# SAMC21_Xplained_Pro_dual_input_power_sup.net
KiCad netlist of a schematic drawn in Altium Designer
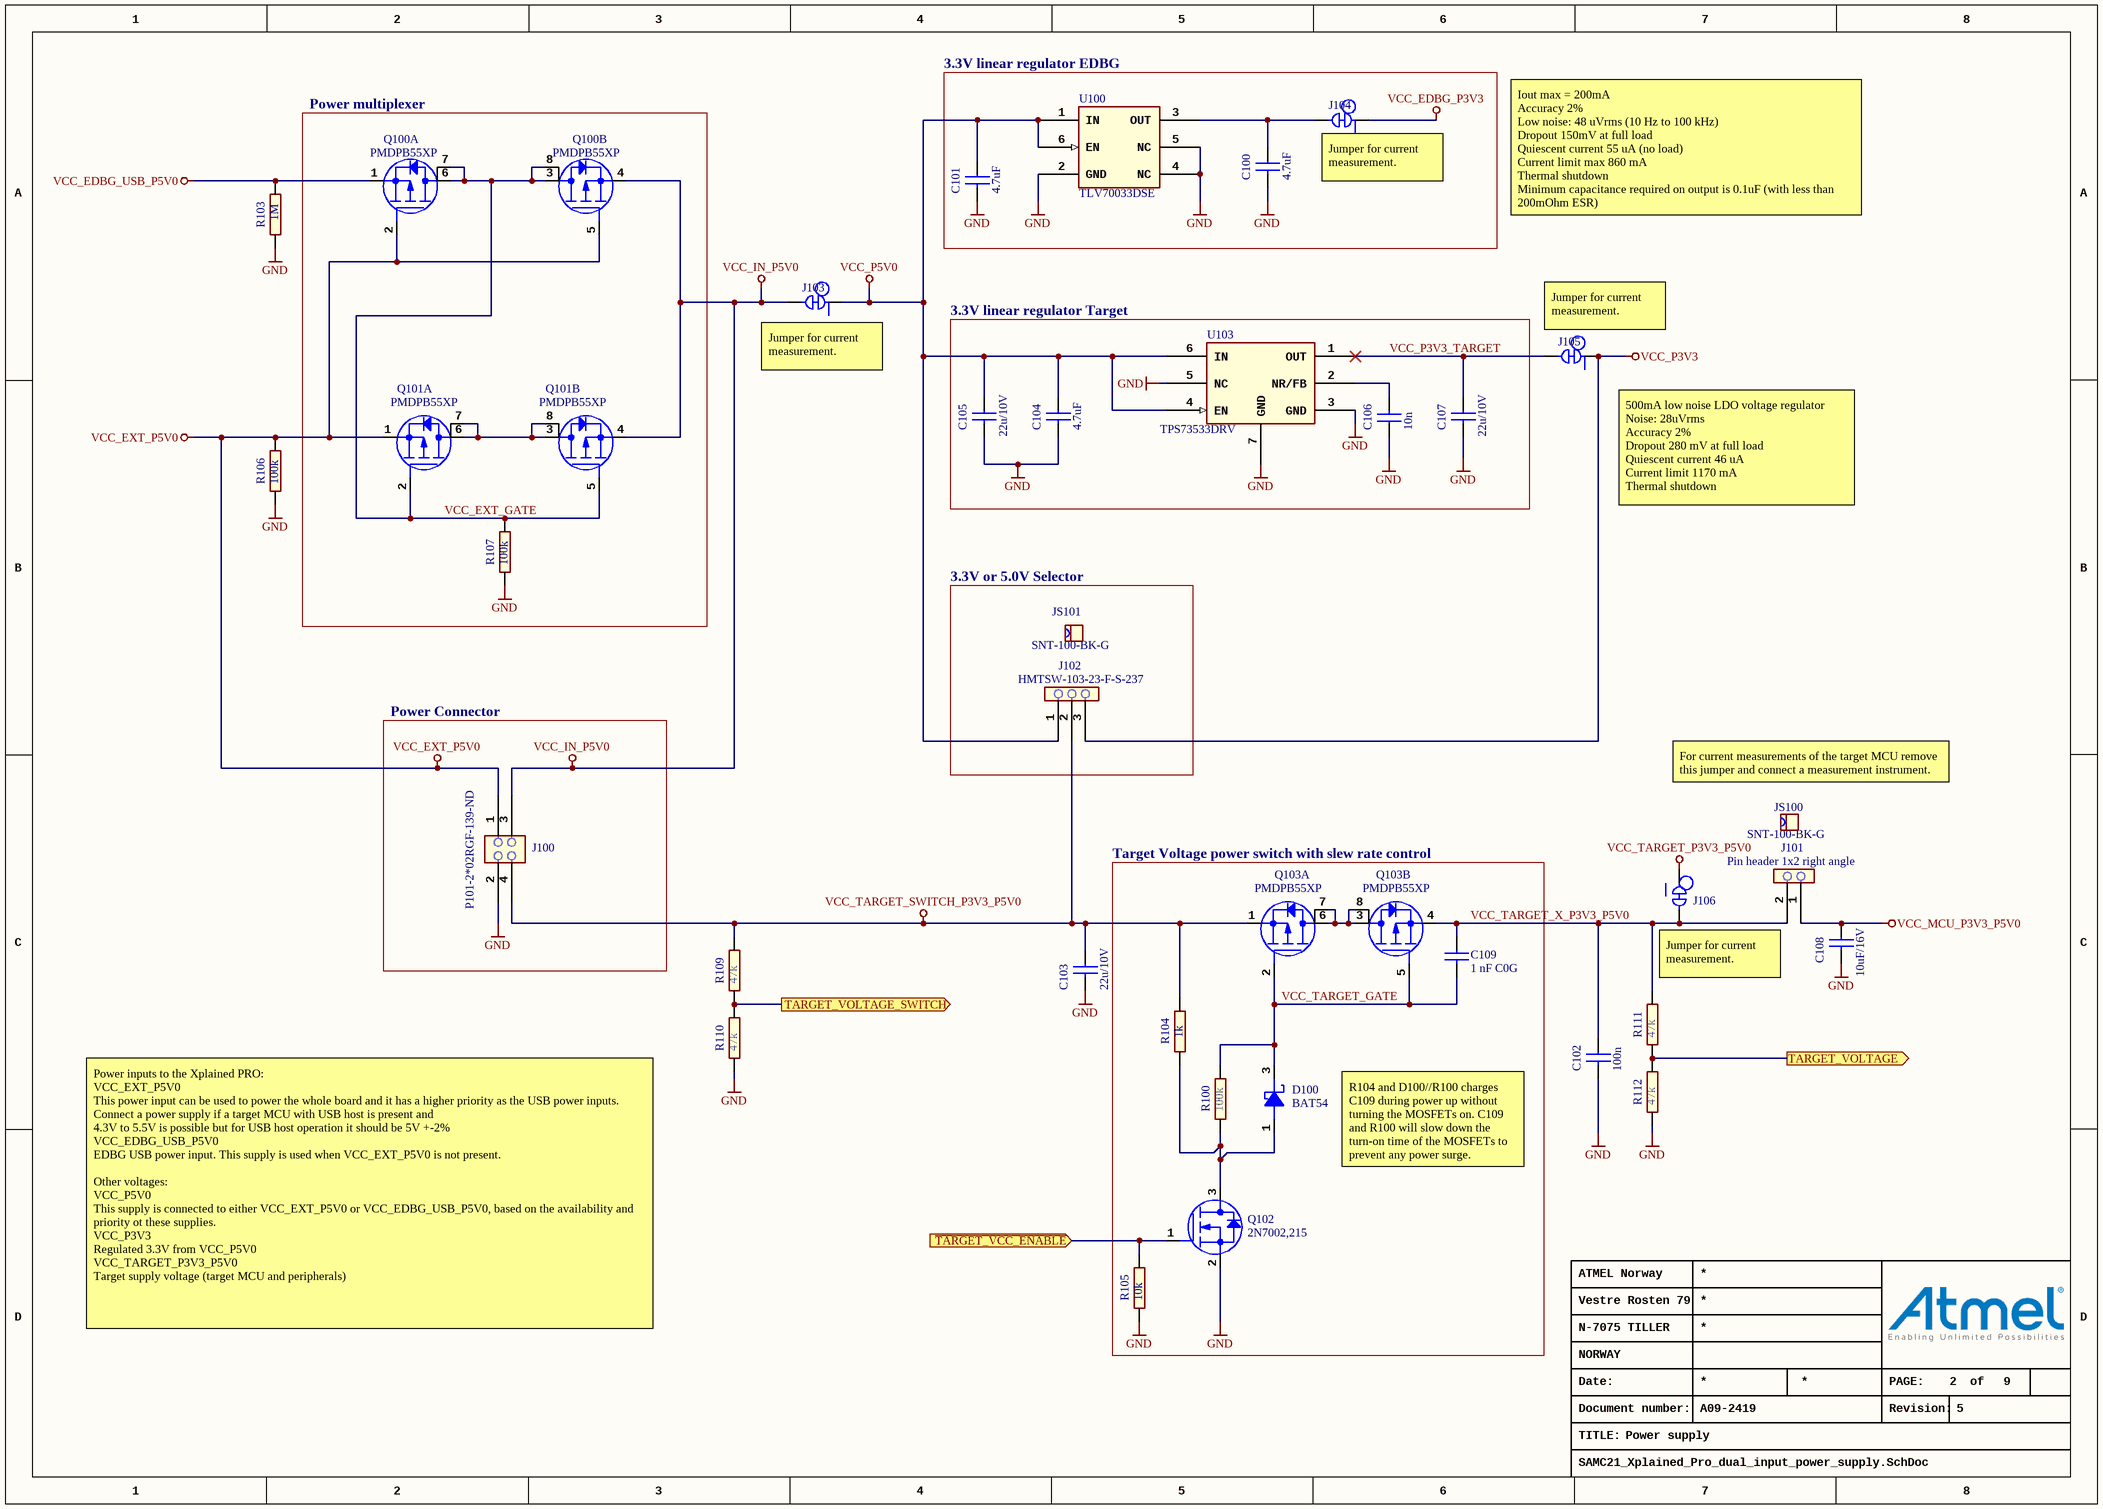
[diagram p0: SAMC21_Xplained_Pro_dual_input_power_supply.SchDoc]

(export (version "E")
  (design (tool "Eeschema 10.0.6"))
  (components
    (comp (ref "C100")
      (value "4.7uF")
      (footprint "AP1-00117")
      (description "Ceramic capacitor, SMD 0603, X5R, 10V, 10% (de31036)")
      (fields (field (name "TOLERANCE") "10%") (field (name "MANUFACTURER") "tdk"))
      (libsource (lib "AltiumDbLib") (part "CAP-NONPOL"))
    )
    (comp (ref "C101")
      (value "4.7uF")
      (footprint "AP1-00117")
      (description "Ceramic capacitor, SMD 0603, X5R, 10V, 10% (de31036)")
      (fields (field (name "TOLERANCE") "10%") (field (name "MANUFACTURER") "tdk"))
      (libsource (lib "AltiumDbLib") (part "CAP-NONPOL"))
    )
    (comp (ref "C102")
      (value "100n")
      (footprint "AP1-00001")
      (description "Ceramic capacitor, SMD 0402, X7R, 16V, +/-10%")
      (fields (field (name "TOLERANCE") "16V, +/-10%") (field (name "MANUFACTURER") "Kemet"))
      (libsource (lib "AltiumDbLib") (part "CAP-NONPOL"))
    )
    (comp (ref "C103")
      (value "22u/10V")
      (footprint "AP1-00003")
      (description "Ceramic capacitor, SMD 0805, X5R, 10V, Â±20%")
      (fields (field (name "MANUFACTURER") "tdk") (field (name "MPN") "C2012X5R1A226M/0.85"))
      (libsource (lib "AltiumDbLib") (part "CAP-NONPOL"))
    )
    (comp (ref "C104")
      (value "4.7uF")
      (footprint "AP1-00117")
      (description "Ceramic capacitor, SMD 0603, X5R, 10V, 10% (de31036)")
      (fields (field (name "TOLERANCE") "10%") (field (name "MANUFACTURER") "tdk"))
      (libsource (lib "AltiumDbLib") (part "CAP-NONPOL"))
    )
    (comp (ref "C105")
      (value "22u/10V")
      (footprint "AP1-00003")
      (description "Ceramic capacitor, SMD 0805, X5R, 10V, Â±20%")
      (fields (field (name "MANUFACTURER") "tdk") (field (name "MPN") "C2012X5R1A226M/0.85"))
      (libsource (lib "AltiumDbLib") (part "CAP-NONPOL"))
    )
    (comp (ref "C106")
      (value "10n")
      (footprint "AP1-00053")
      (description "Ceramic capacitor, SMD 0402, X7R, 25V, +/-10%")
      (fields (field (name "TOLERANCE") "25V, +/-10%"))
      (libsource (lib "AltiumDbLib") (part "CAP-NONPOL"))
    )
    (comp (ref "C107")
      (value "22u/10V")
      (footprint "AP1-00003")
      (description "Ceramic capacitor, SMD 0805, X5R, 10V, Â±20%")
      (fields (field (name "MANUFACTURER") "tdk") (field (name "MPN") "C2012X5R1A226M/0.85"))
      (libsource (lib "AltiumDbLib") (part "CAP-NONPOL"))
    )
    (comp (ref "C108")
      (value "10uF/16V")
      (footprint "AP1-00039")
      (description "Ceramic capacitor, SMD 0603, X5R, 16V, 10UF ± 20% (High Density)")
      (fields (field (name "TOLERANCE") "­± 20%") (field (name "MANUFACTURER") "Taiyo Yuden"))
      (libsource (lib "AltiumDbLib") (part "CAP-NONPOL"))
    )
    (comp (ref "C109")
      (value "1 nF C0G")
      (footprint "AP1-00053")
      (description "Ceramic capacitor, SMD 0402, C0G, 50V, +/-5%")
      (fields (field (name "TOLERANCE") "5%") (field (name "MANUFACTURER") "Murata"))
      (libsource (lib "AltiumDbLib") (part "CAP-NONPOL"))
    )
    (comp (ref "D100")
      (value "BAT54")
      (footprint "AP4-00007")
      (fields (field (name "MANUFACTURER") "Philips"))
      (libsource (lib "AltiumDbLib") (part "SCHOTTKY_SMD_31"))
    )
    (comp (ref "J100")
      (value "P101-2*02RGF-139-ND")
      (footprint "AP8-00628")
      (description "Pin header, 2x2, Right Angle, 2.54mm, THT, Pin In Paste")
      (fields (field (name "MANUFACTURER") "Pro-data International Corp"))
      (libsource (lib "AltiumDbLib") (part "HEADER 2x2"))
    )
    (comp (ref "J101")
      (value "Pin header 1x2 right angle")
      (footprint "AP8-00367")
      (description "1x2 pin header, right angle, 2.54 mm pitch, through-hole")
      (fields (field (name "MANUFACTURER") "Pro-data International Corp") (field (name "MPN") "2213R-2G"))
      (libsource (lib "AltiumDbLib") (part "HEADER 1x2"))
    )
    (comp (ref "J102")
      (value "HMTSW-103-23-F-S-237")
      (footprint "AP8-00745")
      (description "1x3 pin header, 2.54mm pitch, Pin-in-Paste THM, 1mm hole")
      (fields (field (name "MANUFACTURER") "SAMTEC"))
      (libsource (lib "AltiumDbLib") (part "HEADER 1x3"))
    )
    (comp (ref "J103")
      (value "~")
      (footprint "AP9-00044")
      (description "Default closed SMD strap, 0603 size")
      (libsource (lib "AltiumDbLib") (part "SMD-STRAP_CLOSED"))
    )
    (comp (ref "J104")
      (value "~")
      (footprint "AP9-00044")
      (description "Default closed SMD strap, 0603 size")
      (libsource (lib "AltiumDbLib") (part "SMD-STRAP_CLOSED"))
    )
    (comp (ref "J105")
      (value "~")
      (footprint "AP9-00044")
      (description "Default closed SMD strap, 0603 size")
      (libsource (lib "AltiumDbLib") (part "SMD-STRAP_CLOSED"))
    )
    (comp (ref "J106")
      (value "~")
      (footprint "AP9-00044")
      (description "Default closed SMD strap, 0603 size")
      (libsource (lib "AltiumDbLib") (part "SMD-STRAP_CLOSED"))
    )
    (comp (ref "JS100")
      (value "SNT-100-BK-G")
      (footprint "AP8-00525")
      (description "Jumper cap for 2.54mm pinheader")
      (fields (field (name "MANUFACTURER") "SAMTEC"))
      (libsource (lib "AltiumDbLib") (part "JUMPER_CAP"))
    )
    (comp (ref "JS101")
      (value "SNT-100-BK-G")
      (footprint "AP8-00525")
      (description "Jumper cap for 2.54mm pinheader")
      (fields (field (name "MANUFACTURER") "SAMTEC"))
      (libsource (lib "AltiumDbLib") (part "JUMPER_CAP"))
    )
    (comp (ref "Q100")
      (value "PMDPB55XP")
      (footprint "AP5-00047")
      (description "Dual P-Channel MOSFET, -20V, RDS(ON) < 55 mOhm @-3.4A@-4.5V")
      (fields (field (name "MANUFACTURER") "NXP") (field (name "Comment") "Farnell order code: 2191806"))
      (libsource (lib "AltiumDbLib") (part "MOSFET_DUAL_P_S1G1D2S2G2D1D1D2"))
    )
    (comp (ref "Q101")
      (value "PMDPB55XP")
      (footprint "AP5-00047")
      (description "Dual P-Channel MOSFET, -20V, RDS(ON) < 55 mOhm @-3.4A@-4.5V")
      (fields (field (name "MANUFACTURER") "NXP") (field (name "Comment") "Farnell order code: 2191806"))
      (libsource (lib "AltiumDbLib") (part "MOSFET_DUAL_P_S1G1D2S2G2D1D1D2"))
    )
    (comp (ref "Q102")
      (value "2N7002,215")
      (footprint "AP5-00002")
      (description "N-Channel MOSFET. 60V, 0.300A continuous, 1.2A Peak. RDS(ON) = 3.8Ohm@VGS=4.5V, VGS(th)<2.5V")
      (fields (field (name "MANUFACTURER") "NXP"))
      (libsource (lib "AltiumDbLib") (part "MOSFET_N_GSD"))
    )
    (comp (ref "Q103")
      (value "PMDPB55XP")
      (footprint "AP5-00047")
      (description "Dual P-Channel MOSFET, -20V, RDS(ON) < 55 mOhm @-3.4A@-4.5V")
      (fields (field (name "MANUFACTURER") "NXP") (field (name "Comment") "Farnell order code: 2191806"))
      (libsource (lib "AltiumDbLib") (part "MOSFET_DUAL_P_S1G1D2S2G2D1D1D2"))
    )
    (comp (ref "R100")
      (value "100k")
      (footprint "AP2-00000")
      (description "Thick film resistor, SMD 0402, 1/16W, 1%")
      (fields (field (name "TOLERANCE") "1 %"))
      (libsource (lib "") (part "R2_1"))
    )
    (comp (ref "R103")
      (value "1M")
      (footprint "AP2-00000")
      (description "Thick film resistor, SMD 0402, 1/16W, 1%")
      (fields (field (name "TOLERANCE") "1 %"))
      (libsource (lib "") (part "R2_1"))
    )
    (comp (ref "R104")
      (value "1k")
      (footprint "AP2-00000")
      (description "Thick film resistor, SMD 0402, 1/16W, 1%")
      (fields (field (name "TOLERANCE") "1 %"))
      (libsource (lib "") (part "R2_1"))
    )
    (comp (ref "R105")
      (value "10k")
      (footprint "AP2-00000")
      (description "Thick film resistor, SMD 0402, 1/16W, 1%")
      (fields (field (name "TOLERANCE") "1 %") (field (name "MANUFACTURER") "vishay"))
      (libsource (lib "") (part "R2_1"))
    )
    (comp (ref "R106")
      (value "100k")
      (footprint "AP2-00000")
      (description "Thick film resistor, SMD 0402, 1/16W, 1%")
      (fields (field (name "TOLERANCE") "1 %"))
      (libsource (lib "") (part "R2_1"))
    )
    (comp (ref "R107")
      (value "100k")
      (footprint "AP2-00000")
      (description "Thick film resistor, SMD 0402, 1/16W, 1%")
      (fields (field (name "TOLERANCE") "1 %"))
      (libsource (lib "") (part "R2_1"))
    )
    (comp (ref "R109")
      (value "47k")
      (footprint "AP2-00000")
      (description "Thick film resistor, SMD 0402, 1/16W, 1%")
      (fields (field (name "TOLERANCE") "1 %"))
      (libsource (lib "AltiumDbLib") (part "R2"))
    )
    (comp (ref "R110")
      (value "47k")
      (footprint "AP2-00000")
      (description "Thick film resistor, SMD 0402, 1/16W, 1%")
      (fields (field (name "TOLERANCE") "1 %"))
      (libsource (lib "AltiumDbLib") (part "R2"))
    )
    (comp (ref "R111")
      (value "47k")
      (footprint "AP2-00000")
      (description "Thick film resistor, SMD 0402, 1/16W, 1%")
      (fields (field (name "TOLERANCE") "1 %"))
      (libsource (lib "AltiumDbLib") (part "R2"))
    )
    (comp (ref "R112")
      (value "47k")
      (footprint "AP2-00000")
      (description "Thick film resistor, SMD 0402, 1/16W, 1%")
      (fields (field (name "TOLERANCE") "1 %"))
      (libsource (lib "AltiumDbLib") (part "R2"))
    )
    (comp (ref "U100")
      (value "TLV70033DSE")
      (footprint "AP6-00262")
      (description "LDO, 200 mA, Iq=31 uA, Vdo=250mV, Vout=3.3V, VIN= 2 V to 5.5V, SON-6 package")
      (fields (field (name "MANUFACTURER") "Texas Instruments"))
      (libsource (lib "AltiumDbLib") (part "TLV70033"))
    )
    (comp (ref "U103")
      (value "TPS73533DRV")
      (footprint "AP6-00162")
      (fields (field (name "MANUFACTURER") "Texas Instruments"))
      (libsource (lib "AltiumDbLib") (part "TPS735xxDRV"))
    )
  )
  (nets
    (net (code "1") (name "/TARGET_VOLTAGE") (class "Default")
      (node (ref "R111") (pin "1") (pinfunction "1_1") (pintype "passive"))
      (node (ref "R112") (pin "2") (pinfunction "2_2") (pintype "passive"))
    )
    (net (code "2") (name "/TARGET_VOLTAGE_SWITCH") (class "Default")
      (node (ref "R109") (pin "1") (pinfunction "1_1") (pintype "passive"))
      (node (ref "R110") (pin "2") (pinfunction "2_2") (pintype "passive"))
    )
    (net (code "3") (name "/VCC_EXT_GATE") (class "Default")
      (node (ref "Q100") (pin "3") (pinfunction "D2_3") (pintype "passive"))
      (node (ref "Q100") (pin "6") (pinfunction "D1_6") (pintype "passive"))
      (node (ref "Q100") (pin "7") (pinfunction "D1_PAD_7") (pintype "passive"))
      (node (ref "Q100") (pin "8") (pinfunction "D2_PAD_8") (pintype "passive"))
      (node (ref "Q101") (pin "2") (pinfunction "G1_2") (pintype "passive"))
      (node (ref "Q101") (pin "5") (pinfunction "G2_5") (pintype "passive"))
      (node (ref "R107") (pin "2") (pinfunction "2_2") (pintype "passive"))
    )
    (net (code "4") (name "/VCC_P3V3_TARGET") (class "Default")
      (node (ref "C107") (pin "1") (pinfunction "1_1") (pintype "passive"))
      (node (ref "J105") (pin "2") (pinfunction "2_2") (pintype "passive"))
      (node (ref "U103") (pin "1") (pinfunction "OUT_1") (pintype "power_in"))
    )
    (net (code "5") (name "/VCC_TARGET_GATE") (class "Default")
      (node (ref "C109") (pin "2") (pinfunction "2_2") (pintype "passive"))
      (node (ref "D100") (pin "3") (pinfunction "CATHODE_3") (pintype "passive"))
      (node (ref "Q103") (pin "2") (pinfunction "G1_2") (pintype "passive"))
      (node (ref "Q103") (pin "5") (pinfunction "G2_5") (pintype "passive"))
      (node (ref "R100") (pin "2") (pinfunction "2_2") (pintype "passive"))
    )
    (net (code "6") (name "/VCC_TARGET_X_P3V3_P5V0") (class "Default")
      (node (ref "C102") (pin "1") (pinfunction "1_1") (pintype "passive"))
      (node (ref "C109") (pin "1") (pinfunction "1_1") (pintype "passive"))
      (node (ref "J101") (pin "2") (pinfunction "2_2") (pintype "passive"))
      (node (ref "J106") (pin "2") (pinfunction "2_2") (pintype "passive"))
      (node (ref "Q103") (pin "4") (pinfunction "S2_4") (pintype "passive"))
      (node (ref "R111") (pin "2") (pinfunction "2_2") (pintype "passive"))
    )
    (net (code "7") (name "/~{TARGET_VCC_ENABLE}") (class "Default")
      (node (ref "Q102") (pin "1") (pinfunction "G_1") (pintype "passive"))
      (node (ref "R105") (pin "2") (pinfunction "2_2") (pintype "passive"))
    )
    (net (code "8") (name "GND") (class "Default")
      (node (ref "C100") (pin "2") (pinfunction "2_2") (pintype "passive"))
      (node (ref "C101") (pin "2") (pinfunction "2_2") (pintype "passive"))
      (node (ref "C102") (pin "2") (pinfunction "2_2") (pintype "passive"))
      (node (ref "C103") (pin "2") (pinfunction "2_2") (pintype "passive"))
      (node (ref "C104") (pin "2") (pinfunction "2_2") (pintype "passive"))
      (node (ref "C105") (pin "2") (pinfunction "2_2") (pintype "passive"))
      (node (ref "C106") (pin "1") (pinfunction "1_1") (pintype "passive"))
      (node (ref "C107") (pin "2") (pinfunction "2_2") (pintype "passive"))
      (node (ref "C108") (pin "2") (pinfunction "2_2") (pintype "passive"))
      (node (ref "J100") (pin "2") (pinfunction "2_2") (pintype "passive"))
      (node (ref "Q102") (pin "2") (pinfunction "S_2") (pintype "passive"))
      (node (ref "R103") (pin "1") (pinfunction "1_1") (pintype "passive"))
      (node (ref "R105") (pin "1") (pinfunction "1_1") (pintype "passive"))
      (node (ref "R106") (pin "1") (pinfunction "1_1") (pintype "passive"))
      (node (ref "R107") (pin "1") (pinfunction "1_1") (pintype "passive"))
      (node (ref "R110") (pin "1") (pinfunction "1_1") (pintype "passive"))
      (node (ref "R112") (pin "1") (pinfunction "1_1") (pintype "passive"))
      (node (ref "U100") (pin "2") (pinfunction "GND_2") (pintype "power_in"))
      (node (ref "U100") (pin "4") (pinfunction "NC_4") (pintype "passive"))
      (node (ref "U100") (pin "5") (pinfunction "NC_5") (pintype "passive"))
      (node (ref "U103") (pin "3") (pinfunction "GND_3") (pintype "power_in"))
      (node (ref "U103") (pin "5") (pinfunction "NC_5") (pintype "passive"))
      (node (ref "U103") (pin "7") (pinfunction "GND_7") (pintype "power_in"))
    )
    (net (code "9") (name "Net-(D100-ANODE)") (class "Default")
      (node (ref "D100") (pin "1") (pinfunction "ANODE_1") (pintype "passive"))
      (node (ref "Q102") (pin "3") (pinfunction "D_3") (pintype "passive"))
      (node (ref "R100") (pin "1") (pinfunction "1_1") (pintype "passive"))
      (node (ref "R104") (pin "1") (pinfunction "1_1") (pintype "passive"))
    )
    (net (code "10") (name "Net-(Q101A-D1)") (class "Default")
      (node (ref "Q101") (pin "3") (pinfunction "D2_3") (pintype "passive"))
      (node (ref "Q101") (pin "6") (pinfunction "D1_6") (pintype "passive"))
      (node (ref "Q101") (pin "7") (pinfunction "D1_PAD_7") (pintype "passive"))
      (node (ref "Q101") (pin "8") (pinfunction "D2_PAD_8") (pintype "passive"))
    )
    (net (code "11") (name "Net-(Q103A-D1)") (class "Default")
      (node (ref "Q103") (pin "3") (pinfunction "D2_3") (pintype "passive"))
      (node (ref "Q103") (pin "6") (pinfunction "D1_6") (pintype "passive"))
      (node (ref "Q103") (pin "7") (pinfunction "D1_PAD_7") (pintype "passive"))
      (node (ref "Q103") (pin "8") (pinfunction "D2_PAD_8") (pintype "passive"))
    )
    (net (code "12") (name "Net-(U100-OUT)") (class "Default")
      (node (ref "C100") (pin "1") (pinfunction "1_1") (pintype "passive"))
      (node (ref "J104") (pin "2") (pinfunction "2_2") (pintype "passive"))
      (node (ref "U100") (pin "3") (pinfunction "OUT_3") (pintype "power_in"))
    )
    (net (code "13") (name "Net-(U103-NR{slash}FB)") (class "Default")
      (node (ref "C106") (pin "2") (pinfunction "2_2") (pintype "passive"))
      (node (ref "U103") (pin "2") (pinfunction "NR/FB_2") (pintype "passive"))
    )
    (net (code "14") (name "VCC_EDBG_P3V3") (class "Default")
      (node (ref "J104") (pin "1") (pinfunction "1_1") (pintype "passive"))
    )
    (net (code "15") (name "VCC_EDBG_USB_P5V0") (class "Default")
      (node (ref "Q100") (pin "1") (pinfunction "S1_1") (pintype "passive"))
      (node (ref "R103") (pin "2") (pinfunction "2_2") (pintype "passive"))
    )
    (net (code "16") (name "VCC_EXT_P5V0") (class "Default")
      (node (ref "J100") (pin "1") (pinfunction "1_1") (pintype "passive"))
      (node (ref "Q100") (pin "2") (pinfunction "G1_2") (pintype "passive"))
      (node (ref "Q100") (pin "5") (pinfunction "G2_5") (pintype "passive"))
      (node (ref "Q101") (pin "1") (pinfunction "S1_1") (pintype "passive"))
      (node (ref "R106") (pin "2") (pinfunction "2_2") (pintype "passive"))
    )
    (net (code "17") (name "VCC_IN_P5V0") (class "Default")
      (node (ref "J100") (pin "3") (pinfunction "3_3") (pintype "passive"))
      (node (ref "J103") (pin "2") (pinfunction "2_2") (pintype "passive"))
      (node (ref "Q100") (pin "4") (pinfunction "S2_4") (pintype "passive"))
      (node (ref "Q101") (pin "4") (pinfunction "S2_4") (pintype "passive"))
    )
    (net (code "18") (name "VCC_MCU_P3V3_P5V0") (class "Default")
      (node (ref "C108") (pin "1") (pinfunction "1_1") (pintype "passive"))
      (node (ref "J101") (pin "1") (pinfunction "1_1") (pintype "passive"))
    )
    (net (code "19") (name "VCC_P3V3") (class "Default")
      (node (ref "J102") (pin "3") (pinfunction "3_3") (pintype "passive"))
      (node (ref "J105") (pin "1") (pinfunction "1_1") (pintype "passive"))
    )
    (net (code "20") (name "VCC_P5V0") (class "Default")
      (node (ref "C101") (pin "1") (pinfunction "1_1") (pintype "passive"))
      (node (ref "C104") (pin "1") (pinfunction "1_1") (pintype "passive"))
      (node (ref "C105") (pin "1") (pinfunction "1_1") (pintype "passive"))
      (node (ref "J102") (pin "1") (pinfunction "1_1") (pintype "passive"))
      (node (ref "J103") (pin "1") (pinfunction "1_1") (pintype "passive"))
      (node (ref "U100") (pin "1") (pinfunction "IN_1") (pintype "power_in"))
      (node (ref "U100") (pin "6") (pinfunction "EN_6") (pintype "input"))
      (node (ref "U103") (pin "4") (pinfunction "EN_4") (pintype "input"))
      (node (ref "U103") (pin "6") (pinfunction "IN_6") (pintype "power_in"))
    )
    (net (code "21") (name "VCC_TARGET_P3V3_P5V0") (class "Default")
      (node (ref "J106") (pin "1") (pinfunction "1_1") (pintype "passive"))
    )
    (net (code "22") (name "VCC_TARGET_SWITCH_P3V3_P5V0") (class "Default")
      (node (ref "C103") (pin "1") (pinfunction "1_1") (pintype "passive"))
      (node (ref "J100") (pin "4") (pinfunction "4_4") (pintype "passive"))
      (node (ref "J102") (pin "2") (pinfunction "2_2") (pintype "passive"))
      (node (ref "Q103") (pin "1") (pinfunction "S1_1") (pintype "passive"))
      (node (ref "R104") (pin "2") (pinfunction "2_2") (pintype "passive"))
      (node (ref "R109") (pin "2") (pinfunction "2_2") (pintype "passive"))
    )
  )
)
